# 2.net
KiCad netlist of a schematic drawn in Altium Designer
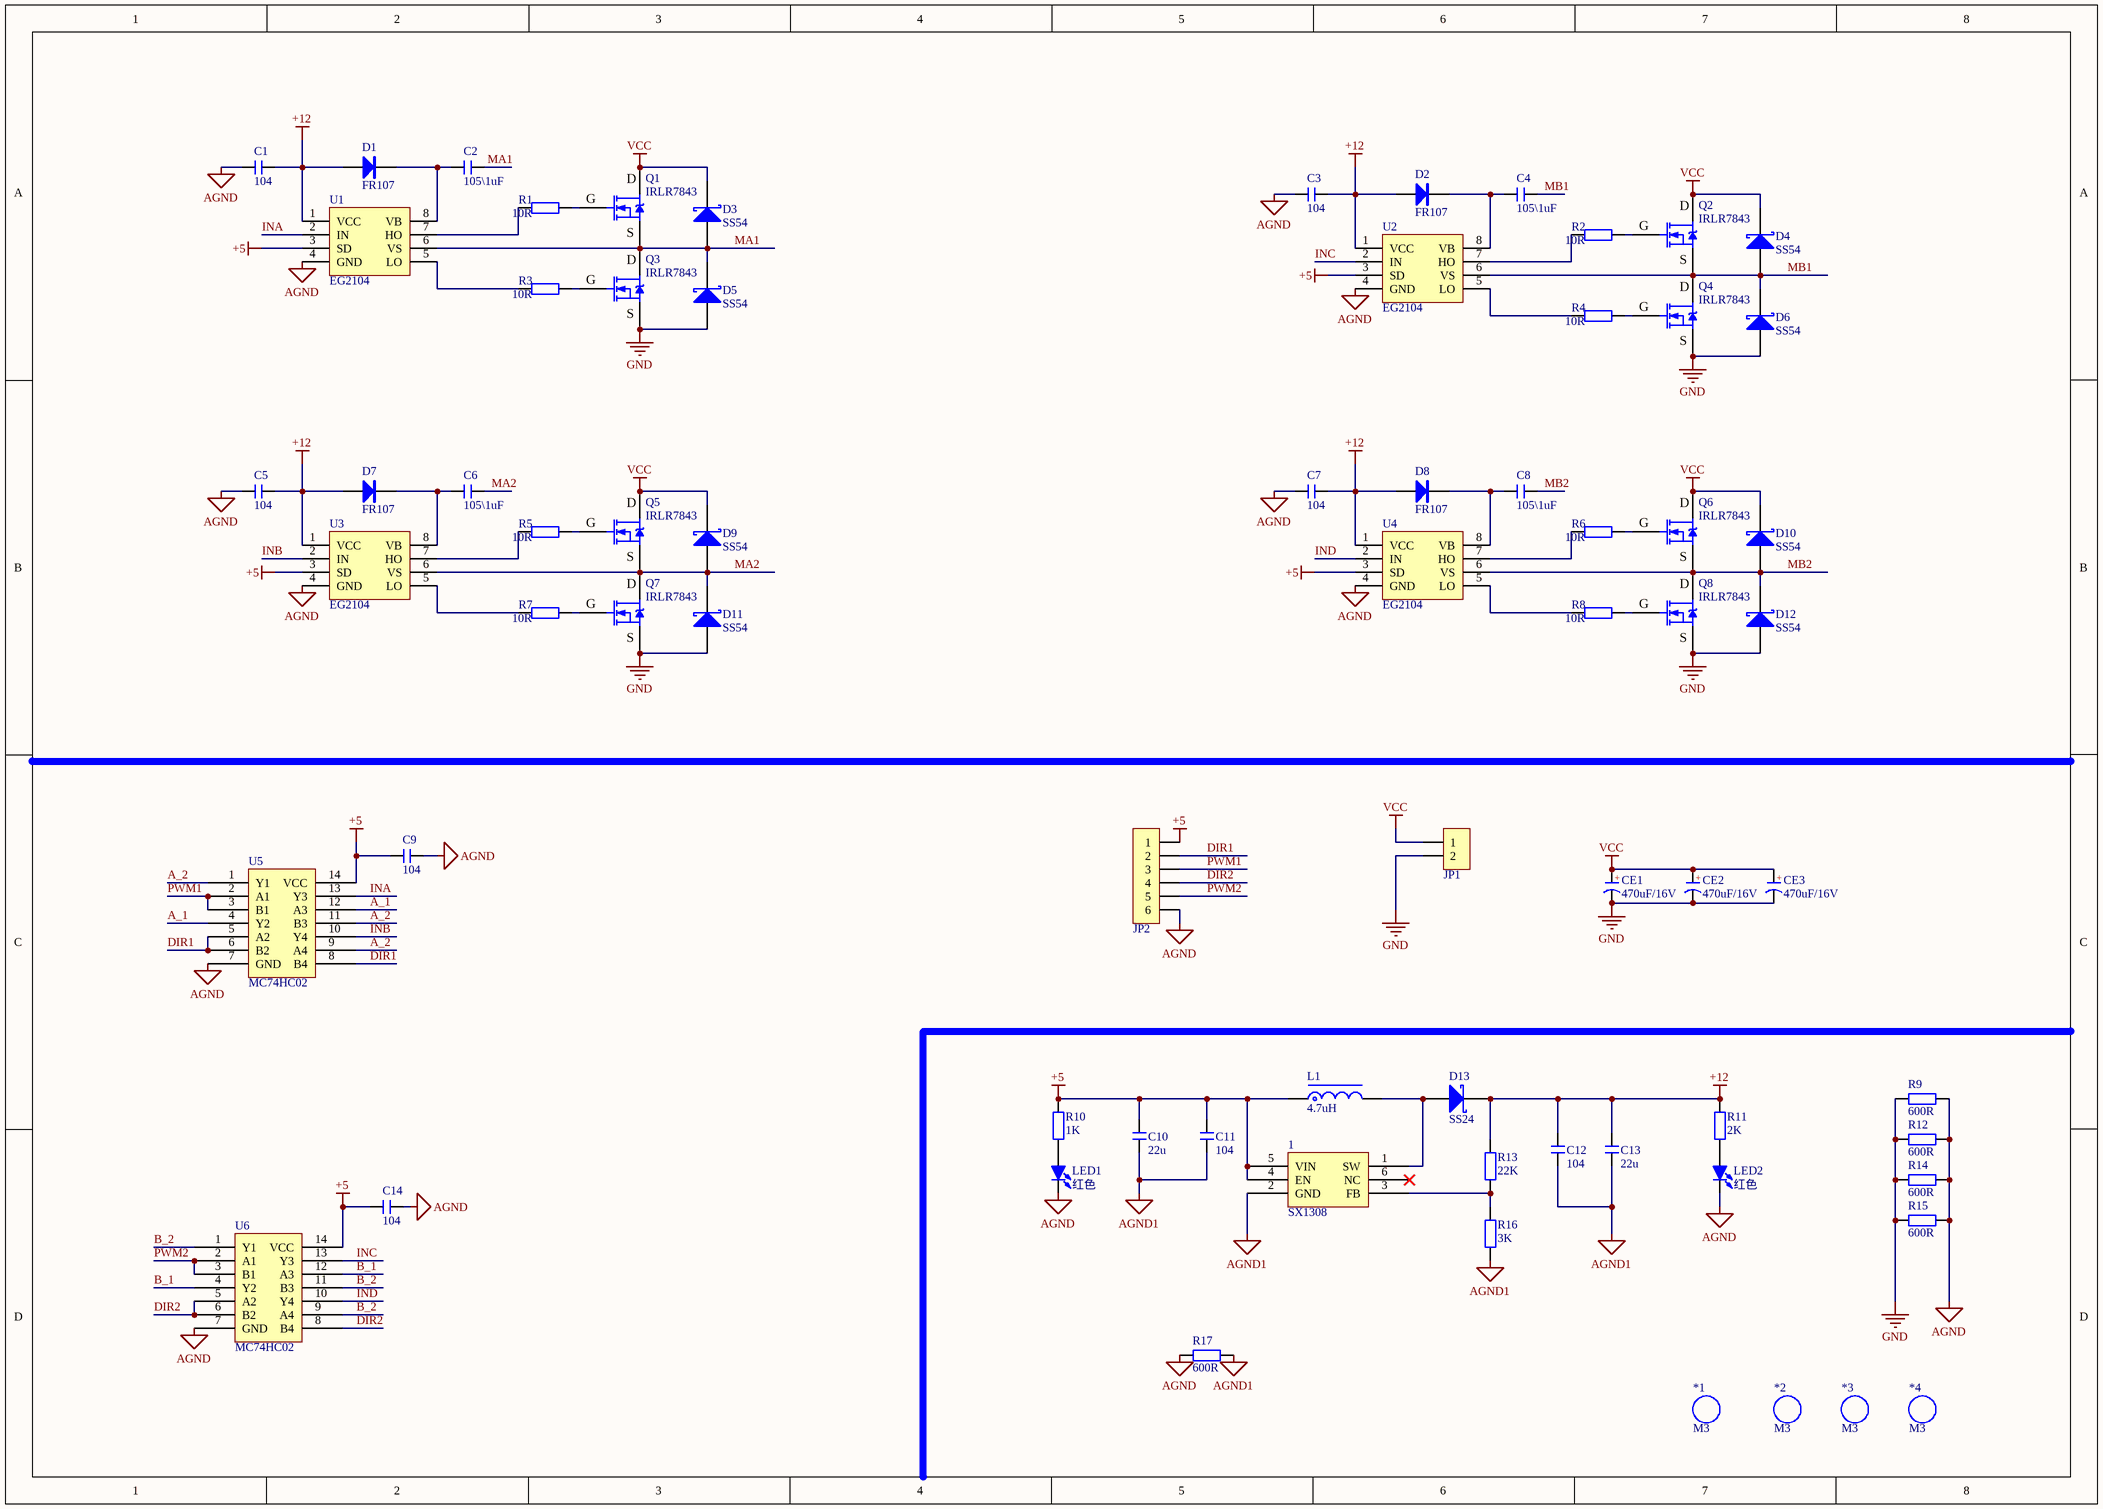
[diagram p0: 双电机驱动版本2.SchDoc]

(export (version "E")
  (design (tool "Eeschema 10.0.6"))
  (components
    (comp (ref "*1")
      (value "M3")
      (footprint "M3 125X200")
      (description "铜柱孔")
      (fields (field (name "版权归属") "封装库来自淘宝 ID：黄晶宝石"))
      (libsource (lib "4.1 - 未分类器件") (part "M3"))
    )
    (comp (ref "*2")
      (value "M3")
      (footprint "M3 125X200")
      (description "铜柱孔")
      (fields (field (name "版权归属") "封装库来自淘宝 ID：黄晶宝石"))
      (libsource (lib "4.1 - 未分类器件") (part "M3"))
    )
    (comp (ref "*3")
      (value "M3")
      (footprint "M3 125X200")
      (description "铜柱孔")
      (fields (field (name "版权归属") "封装库来自淘宝 ID：黄晶宝石"))
      (libsource (lib "4.1 - 未分类器件") (part "M3"))
    )
    (comp (ref "*4")
      (value "M3")
      (footprint "M3 125X200")
      (description "铜柱孔")
      (fields (field (name "版权归属") "封装库来自淘宝 ID：黄晶宝石"))
      (libsource (lib "4.1 - 未分类器件") (part "M3"))
    )
    (comp (ref "1") (value "SX1308") (footprint "SOT23-6L") (libsource (lib "boost电源5V") (part "SX1308")))
    (comp (ref "C1")
      (value "104")
      (footprint "C 0805_L")
      (description "贴片电容")
      (libsource (lib "0.1 - 电阻-电容-电感") (part "C"))
    )
    (comp (ref "C2")
      (value "10~{5}1uF")
      (footprint "C 0805_L")
      (description "贴片电容")
      (libsource (lib "0.1 - 电阻-电容-电感") (part "C"))
    )
    (comp (ref "C3")
      (value "104")
      (footprint "C 0805_L")
      (description "贴片电容")
      (libsource (lib "0.1 - 电阻-电容-电感") (part "C"))
    )
    (comp (ref "C4")
      (value "10~{5}1uF")
      (footprint "C 0805_L")
      (description "贴片电容")
      (libsource (lib "0.1 - 电阻-电容-电感") (part "C"))
    )
    (comp (ref "C5")
      (value "104")
      (footprint "C 0805_L")
      (description "贴片电容")
      (libsource (lib "0.1 - 电阻-电容-电感") (part "C"))
    )
    (comp (ref "C6")
      (value "10~{5}1uF")
      (footprint "C 0805_L")
      (description "贴片电容")
      (libsource (lib "0.1 - 电阻-电容-电感") (part "C"))
    )
    (comp (ref "C7")
      (value "104")
      (footprint "C 0805_L")
      (description "贴片电容")
      (libsource (lib "0.1 - 电阻-电容-电感") (part "C"))
    )
    (comp (ref "C8")
      (value "10~{5}1uF")
      (footprint "C 0805_L")
      (description "贴片电容")
      (libsource (lib "0.1 - 电阻-电容-电感") (part "C"))
    )
    (comp (ref "C9")
      (value "104")
      (footprint "C 0603_L")
      (description "贴片电容")
      (libsource (lib "0.1 - 电阻-电容-电感") (part "C"))
    )
    (comp (ref "C10")
      (value "22u")
      (footprint "C 0805_L")
      (description "贴片电容")
      (libsource (lib "0.1 - 电阻-电容-电感") (part "C"))
    )
    (comp (ref "C11")
      (value "104")
      (footprint "C 0603_L")
      (description "贴片电容")
      (libsource (lib "0.1 - 电阻-电容-电感") (part "C"))
    )
    (comp (ref "C12")
      (value "104")
      (footprint "C 0603_L")
      (description "贴片电容")
      (libsource (lib "0.1 - 电阻-电容-电感") (part "C"))
    )
    (comp (ref "C13")
      (value "22u")
      (footprint "C 0805_L")
      (description "贴片电容")
      (libsource (lib "0.1 - 电阻-电容-电感") (part "C"))
    )
    (comp (ref "C14")
      (value "104")
      (footprint "C 0603_L")
      (description "贴片电容")
      (libsource (lib "0.1 - 电阻-电容-电感") (part "C"))
    )
    (comp (ref "CE1")
      (value "470uF/16V")
      (footprint "CAP 3*8*12")
      (description "直插电解电容")
      (libsource (lib "0.1 - 电阻-电容-电感") (part "CE"))
    )
    (comp (ref "CE2")
      (value "470uF/16V")
      (footprint "CAP 3*8*12")
      (description "直插电解电容")
      (libsource (lib "0.1 - 电阻-电容-电感") (part "CE"))
    )
    (comp (ref "CE3")
      (value "470uF/16V")
      (footprint "CAP 3*8*12")
      (description "直插电解电容")
      (libsource (lib "0.1 - 电阻-电容-电感") (part "CE"))
    )
    (comp (ref "D1")
      (value "FR107")
      (footprint "SOD-123")
      (description "快恢复整流二极管")
      (fields (field (name "版权归属") "封装库来自淘宝 ID：黄晶宝石"))
      (libsource (lib "0.2 - 二极管-整流桥") (part "FR107"))
    )
    (comp (ref "D2")
      (value "FR107")
      (footprint "SOD-123")
      (description "快恢复整流二极管")
      (fields (field (name "版权归属") "封装库来自淘宝 ID：黄晶宝石"))
      (libsource (lib "0.2 - 二极管-整流桥") (part "FR107"))
    )
    (comp (ref "D3")
      (value "SS54")
      (footprint "SMA")
      (description "肖特基二极管")
      (libsource (lib "0.2 - 二极管-整流桥") (part "SS34"))
    )
    (comp (ref "D4")
      (value "SS54")
      (footprint "SMA")
      (description "肖特基二极管")
      (libsource (lib "0.2 - 二极管-整流桥") (part "SS34"))
    )
    (comp (ref "D5")
      (value "SS54")
      (footprint "SMA")
      (description "肖特基二极管")
      (libsource (lib "0.2 - 二极管-整流桥") (part "SS34"))
    )
    (comp (ref "D6")
      (value "SS54")
      (footprint "SMA")
      (description "肖特基二极管")
      (libsource (lib "0.2 - 二极管-整流桥") (part "SS34"))
    )
    (comp (ref "D7")
      (value "FR107")
      (footprint "SOD-123")
      (description "快恢复整流二极管")
      (fields (field (name "版权归属") "封装库来自淘宝 ID：黄晶宝石"))
      (libsource (lib "0.2 - 二极管-整流桥") (part "FR107"))
    )
    (comp (ref "D8")
      (value "FR107")
      (footprint "SOD-123")
      (description "快恢复整流二极管")
      (fields (field (name "版权归属") "封装库来自淘宝 ID：黄晶宝石"))
      (libsource (lib "0.2 - 二极管-整流桥") (part "FR107"))
    )
    (comp (ref "D9")
      (value "SS54")
      (footprint "SMA")
      (description "肖特基二极管")
      (libsource (lib "0.2 - 二极管-整流桥") (part "SS34"))
    )
    (comp (ref "D10")
      (value "SS54")
      (footprint "SMA")
      (description "肖特基二极管")
      (libsource (lib "0.2 - 二极管-整流桥") (part "SS34"))
    )
    (comp (ref "D11")
      (value "SS54")
      (footprint "SMA")
      (description "肖特基二极管")
      (libsource (lib "0.2 - 二极管-整流桥") (part "SS34"))
    )
    (comp (ref "D12")
      (value "SS54")
      (footprint "SMA")
      (description "肖特基二极管")
      (libsource (lib "0.2 - 二极管-整流桥") (part "SS34"))
    )
    (comp (ref "D13")
      (value "SS24")
      (footprint "SMA")
      (description "肖特基二极管")
      (libsource (lib "0.2 - 二极管-整流桥") (part "SS14"))
    )
    (comp (ref "JP1")
      (value "HDR-1X2")
      (footprint "XT30-M")
      (description "2P接插件")
      (fields (field (name "版权归属") "封装库来自淘宝卖家 ID：黄晶宝石"))
      (libsource (lib "6.1 - 接插件-脚距5.08 (200mil) ") (part "Header 2"))
    )
    (comp (ref "JP2")
      (value "HDR-1X6")
      (footprint "XH2.54-WI-6P")
      (description "6P接插件")
      (fields (field (name "版权归属") "封装库来自淘宝 ID：黄晶宝石"))
      (libsource (lib "5.4 - 接插件-脚距2.54 (100mil) ") (part "Header 6"))
    )
    (comp (ref "L1")
      (value "4.7uH")
      (footprint "CD43")
      (description "CD系列贴片线绕功率电感")
      (libsource (lib "0.1 - 电阻-电容-电感") (part "L-SMD"))
    )
    (comp (ref "LED1")
      (value "红色")
      (footprint "LED 0603G")
      (description "贴片LED")
      (fields (field (name "版权归属") "封装库来自淘宝 ID：黄晶宝石"))
      (libsource (lib "0.3 - LED发光二极管") (part "LED-SMD"))
    )
    (comp (ref "LED2")
      (value "红色")
      (footprint "LED 0603R")
      (description "贴片LED")
      (fields (field (name "版权归属") "封装库来自淘宝 ID：黄晶宝石"))
      (libsource (lib "0.3 - LED发光二极管") (part "LED-SMD"))
    )
    (comp (ref "Q1")
      (value "IRLR7843")
      (footprint "TO252")
      (description "N沟场效应管")
      (fields (field (name "版权归属") "封装库来自淘宝 ID：黄晶宝石"))
      (libsource (lib "0.5 - 场效应管-可控硅") (part "IRF3710"))
    )
    (comp (ref "Q2")
      (value "IRLR7843")
      (footprint "TO252")
      (description "N沟场效应管")
      (fields (field (name "版权归属") "封装库来自淘宝 ID：黄晶宝石"))
      (libsource (lib "0.5 - 场效应管-可控硅") (part "IRF3710"))
    )
    (comp (ref "Q3")
      (value "IRLR7843")
      (footprint "TO252")
      (description "N沟场效应管")
      (fields (field (name "版权归属") "封装库来自淘宝 ID：黄晶宝石"))
      (libsource (lib "0.5 - 场效应管-可控硅") (part "IRF3710"))
    )
    (comp (ref "Q4")
      (value "IRLR7843")
      (footprint "TO252")
      (description "N沟场效应管")
      (fields (field (name "版权归属") "封装库来自淘宝 ID：黄晶宝石"))
      (libsource (lib "0.5 - 场效应管-可控硅") (part "IRF3710"))
    )
    (comp (ref "Q5")
      (value "IRLR7843")
      (footprint "TO252")
      (description "N沟场效应管")
      (fields (field (name "版权归属") "封装库来自淘宝 ID：黄晶宝石"))
      (libsource (lib "0.5 - 场效应管-可控硅") (part "IRF3710"))
    )
    (comp (ref "Q6")
      (value "IRLR7843")
      (footprint "TO252")
      (description "N沟场效应管")
      (fields (field (name "版权归属") "封装库来自淘宝 ID：黄晶宝石"))
      (libsource (lib "0.5 - 场效应管-可控硅") (part "IRF3710"))
    )
    (comp (ref "Q7")
      (value "IRLR7843")
      (footprint "TO252")
      (description "N沟场效应管")
      (fields (field (name "版权归属") "封装库来自淘宝 ID：黄晶宝石"))
      (libsource (lib "0.5 - 场效应管-可控硅") (part "IRF3710"))
    )
    (comp (ref "Q8")
      (value "IRLR7843")
      (footprint "TO252")
      (description "N沟场效应管")
      (fields (field (name "版权归属") "封装库来自淘宝 ID：黄晶宝石"))
      (libsource (lib "0.5 - 场效应管-可控硅") (part "IRF3710"))
    )
    (comp (ref "R1")
      (value "10R")
      (footprint "R 0603_L")
      (description "贴片电阻")
      (fields (field (name "版权归属") "来自淘宝 ID：黄晶宝石"))
      (libsource (lib "0.1 - 电阻-电容-电感") (part "R"))
    )
    (comp (ref "R2")
      (value "10R")
      (footprint "R 0603_L")
      (description "贴片电阻")
      (fields (field (name "版权归属") "来自淘宝 ID：黄晶宝石"))
      (libsource (lib "0.1 - 电阻-电容-电感") (part "R"))
    )
    (comp (ref "R3")
      (value "10R")
      (footprint "R 0603_L")
      (description "贴片电阻")
      (fields (field (name "版权归属") "来自淘宝 ID：黄晶宝石"))
      (libsource (lib "0.1 - 电阻-电容-电感") (part "R"))
    )
    (comp (ref "R4")
      (value "10R")
      (footprint "R 0603_L")
      (description "贴片电阻")
      (fields (field (name "版权归属") "来自淘宝 ID：黄晶宝石"))
      (libsource (lib "0.1 - 电阻-电容-电感") (part "R"))
    )
    (comp (ref "R5")
      (value "10R")
      (footprint "R 0603_L")
      (description "贴片电阻")
      (fields (field (name "版权归属") "来自淘宝 ID：黄晶宝石"))
      (libsource (lib "0.1 - 电阻-电容-电感") (part "R"))
    )
    (comp (ref "R6")
      (value "10R")
      (footprint "R 0603_L")
      (description "贴片电阻")
      (fields (field (name "版权归属") "来自淘宝 ID：黄晶宝石"))
      (libsource (lib "0.1 - 电阻-电容-电感") (part "R"))
    )
    (comp (ref "R7")
      (value "10R")
      (footprint "R 0603_L")
      (description "贴片电阻")
      (fields (field (name "版权归属") "来自淘宝 ID：黄晶宝石"))
      (libsource (lib "0.1 - 电阻-电容-电感") (part "R"))
    )
    (comp (ref "R8")
      (value "10R")
      (footprint "R 0603_L")
      (description "贴片电阻")
      (fields (field (name "版权归属") "来自淘宝 ID：黄晶宝石"))
      (libsource (lib "0.1 - 电阻-电容-电感") (part "R"))
    )
    (comp (ref "R9")
      (value "600R")
      (footprint "R 0603_L")
      (description "磁珠")
      (fields (field (name "版权归属") "来自淘宝 ID：黄晶宝石"))
      (libsource (lib "0.1 - 电阻-电容-电感") (part "R"))
    )
    (comp (ref "R10")
      (value "1K")
      (footprint "R 0603_L")
      (description "贴片电阻")
      (fields (field (name "版权归属") "来自淘宝 ID：黄晶宝石"))
      (libsource (lib "0.1 - 电阻-电容-电感") (part "R"))
    )
    (comp (ref "R11")
      (value "2K")
      (footprint "R 0603_L")
      (description "贴片电阻")
      (fields (field (name "版权归属") "来自淘宝 ID：黄晶宝石"))
      (libsource (lib "0.1 - 电阻-电容-电感") (part "R"))
    )
    (comp (ref "R12")
      (value "600R")
      (footprint "R 0603_L")
      (description "磁珠")
      (fields (field (name "版权归属") "来自淘宝 ID：黄晶宝石"))
      (libsource (lib "0.1 - 电阻-电容-电感") (part "R"))
    )
    (comp (ref "R13")
      (value "22K")
      (footprint "R 0603_L")
      (description "贴片电阻")
      (fields (field (name "版权归属") "来自淘宝 ID：黄晶宝石"))
      (libsource (lib "0.1 - 电阻-电容-电感") (part "R"))
    )
    (comp (ref "R14")
      (value "600R")
      (footprint "R 0603_L")
      (description "磁珠")
      (fields (field (name "版权归属") "来自淘宝 ID：黄晶宝石"))
      (libsource (lib "0.1 - 电阻-电容-电感") (part "R"))
    )
    (comp (ref "R15")
      (value "600R")
      (footprint "R 0603_L")
      (description "磁珠")
      (fields (field (name "版权归属") "来自淘宝 ID：黄晶宝石"))
      (libsource (lib "0.1 - 电阻-电容-电感") (part "R"))
    )
    (comp (ref "R16")
      (value "3K")
      (footprint "R 0603_L")
      (description "贴片电阻")
      (fields (field (name "版权归属") "来自淘宝 ID：黄晶宝石"))
      (libsource (lib "0.1 - 电阻-电容-电感") (part "R"))
    )
    (comp (ref "R17")
      (value "600R")
      (footprint "R 0603_L")
      (description "磁珠")
      (fields (field (name "版权归属") "来自淘宝 ID：黄晶宝石"))
      (libsource (lib "0.1 - 电阻-电容-电感") (part "R"))
    )
    (comp (ref "U1")
      (value "EG2104")
      (footprint "SOP8")
      (description "半桥驱动芯片")
      (libsource (lib "1.1 - 电源类芯片") (part "EG2104"))
    )
    (comp (ref "U2")
      (value "EG2104")
      (footprint "SOP8")
      (description "半桥驱动芯片")
      (libsource (lib "1.1 - 电源类芯片") (part "EG2104"))
    )
    (comp (ref "U3")
      (value "EG2104")
      (footprint "SOP8")
      (description "半桥驱动芯片")
      (libsource (lib "1.1 - 电源类芯片") (part "EG2104"))
    )
    (comp (ref "U4")
      (value "EG2104")
      (footprint "SOP8")
      (description "半桥驱动芯片")
      (libsource (lib "1.1 - 电源类芯片") (part "EG2104"))
    )
    (comp (ref "U5")
      (value "MC74HC02")
      (footprint "SOP14_N")
      (description "或非门")
      (libsource (lib "智能车驱动-双电机-版本1") (part "MC74HC02"))
    )
    (comp (ref "U6")
      (value "MC74HC02")
      (footprint "SOP14_N")
      (description "或非门")
      (libsource (lib "智能车驱动-双电机-版本1") (part "MC74HC02"))
    )
  )
  (nets
    (net (code "1") (name "+5") (class "Default")
      (node (ref "1") (pin "4") (pinfunction "EN_4") (pintype "passive"))
      (node (ref "1") (pin "5") (pinfunction "VIN_5") (pintype "passive"))
      (node (ref "C10") (pin "2") (pinfunction "2_2") (pintype "passive"))
      (node (ref "C11") (pin "2") (pinfunction "2_2") (pintype "passive"))
      (node (ref "C14") (pin "1") (pinfunction "1_1") (pintype "passive"))
      (node (ref "C9") (pin "1") (pinfunction "1_1") (pintype "passive"))
      (node (ref "JP2") (pin "1") (pinfunction "1_1") (pintype "passive"))
      (node (ref "L1") (pin "1") (pinfunction "1_1") (pintype "passive"))
      (node (ref "R10") (pin "2") (pinfunction "2_2") (pintype "passive"))
      (node (ref "U1") (pin "3") (pinfunction "SD_3") (pintype "passive"))
      (node (ref "U2") (pin "3") (pinfunction "SD_3") (pintype "passive"))
      (node (ref "U3") (pin "3") (pinfunction "SD_3") (pintype "passive"))
      (node (ref "U4") (pin "3") (pinfunction "SD_3") (pintype "passive"))
      (node (ref "U5") (pin "14") (pinfunction "VCC_14") (pintype "passive"))
      (node (ref "U6") (pin "14") (pinfunction "VCC_14") (pintype "passive"))
    )
    (net (code "2") (name "+12") (class "Default")
      (node (ref "C1") (pin "2") (pinfunction "2_2") (pintype "passive"))
      (node (ref "C12") (pin "2") (pinfunction "2_2") (pintype "passive"))
      (node (ref "C13") (pin "2") (pinfunction "2_2") (pintype "passive"))
      (node (ref "C3") (pin "2") (pinfunction "2_2") (pintype "passive"))
      (node (ref "C5") (pin "2") (pinfunction "2_2") (pintype "passive"))
      (node (ref "C7") (pin "2") (pinfunction "2_2") (pintype "passive"))
      (node (ref "D1") (pin "1") (pinfunction "A_1") (pintype "passive"))
      (node (ref "D13") (pin "2") (pinfunction "K_2") (pintype "passive"))
      (node (ref "D2") (pin "1") (pinfunction "A_1") (pintype "passive"))
      (node (ref "D7") (pin "1") (pinfunction "A_1") (pintype "passive"))
      (node (ref "D8") (pin "1") (pinfunction "A_1") (pintype "passive"))
      (node (ref "R11") (pin "2") (pinfunction "2_2") (pintype "passive"))
      (node (ref "R13") (pin "2") (pinfunction "2_2") (pintype "passive"))
      (node (ref "U1") (pin "1") (pinfunction "VCC_1") (pintype "passive"))
      (node (ref "U2") (pin "1") (pinfunction "VCC_1") (pintype "passive"))
      (node (ref "U3") (pin "1") (pinfunction "VCC_1") (pintype "passive"))
      (node (ref "U4") (pin "1") (pinfunction "VCC_1") (pintype "passive"))
    )
    (net (code "3") (name "/A_1") (class "Default")
      (node (ref "U5") (pin "12") (pinfunction "A3_12") (pintype "passive"))
      (node (ref "U5") (pin "4") (pinfunction "Y2_4") (pintype "passive"))
    )
    (net (code "4") (name "/A_2") (class "Default")
      (node (ref "U5") (pin "1") (pinfunction "Y1_1") (pintype "passive"))
      (node (ref "U5") (pin "11") (pinfunction "B3_11") (pintype "passive"))
      (node (ref "U5") (pin "9") (pinfunction "A4_9") (pintype "passive"))
    )
    (net (code "5") (name "/B_1") (class "Default")
      (node (ref "U6") (pin "12") (pinfunction "A3_12") (pintype "passive"))
      (node (ref "U6") (pin "4") (pinfunction "Y2_4") (pintype "passive"))
    )
    (net (code "6") (name "/B_2") (class "Default")
      (node (ref "U6") (pin "1") (pinfunction "Y1_1") (pintype "passive"))
      (node (ref "U6") (pin "11") (pinfunction "B3_11") (pintype "passive"))
      (node (ref "U6") (pin "9") (pinfunction "A4_9") (pintype "passive"))
    )
    (net (code "7") (name "/DIR1") (class "Default")
      (node (ref "JP2") (pin "2") (pinfunction "2_2") (pintype "passive"))
      (node (ref "U5") (pin "5") (pinfunction "A2_5") (pintype "passive"))
      (node (ref "U5") (pin "6") (pinfunction "B2_6") (pintype "passive"))
      (node (ref "U5") (pin "8") (pinfunction "B4_8") (pintype "passive"))
    )
    (net (code "8") (name "/DIR2") (class "Default")
      (node (ref "JP2") (pin "4") (pinfunction "4_4") (pintype "passive"))
      (node (ref "U6") (pin "5") (pinfunction "A2_5") (pintype "passive"))
      (node (ref "U6") (pin "6") (pinfunction "B2_6") (pintype "passive"))
      (node (ref "U6") (pin "8") (pinfunction "B4_8") (pintype "passive"))
    )
    (net (code "9") (name "/INA") (class "Default")
      (node (ref "U1") (pin "2") (pinfunction "IN_2") (pintype "passive"))
      (node (ref "U5") (pin "13") (pinfunction "Y3_13") (pintype "passive"))
    )
    (net (code "10") (name "/INB") (class "Default")
      (node (ref "U3") (pin "2") (pinfunction "IN_2") (pintype "passive"))
      (node (ref "U5") (pin "10") (pinfunction "Y4_10") (pintype "passive"))
    )
    (net (code "11") (name "/INC") (class "Default")
      (node (ref "U2") (pin "2") (pinfunction "IN_2") (pintype "passive"))
      (node (ref "U6") (pin "13") (pinfunction "Y3_13") (pintype "passive"))
    )
    (net (code "12") (name "/IND") (class "Default")
      (node (ref "U4") (pin "2") (pinfunction "IN_2") (pintype "passive"))
      (node (ref "U6") (pin "10") (pinfunction "Y4_10") (pintype "passive"))
    )
    (net (code "13") (name "/MA1") (class "Default")
      (node (ref "C2") (pin "1") (pinfunction "1_1") (pintype "passive"))
      (node (ref "D3") (pin "1") (pinfunction "A_1") (pintype "passive"))
      (node (ref "D5") (pin "2") (pinfunction "K_2") (pintype "passive"))
      (node (ref "Q1") (pin "3") (pinfunction "S_3") (pintype "passive"))
      (node (ref "Q3") (pin "2") (pinfunction "D_2") (pintype "passive"))
      (node (ref "U1") (pin "6") (pinfunction "VS_6") (pintype "passive"))
    )
    (net (code "14") (name "/MA2") (class "Default")
      (node (ref "C6") (pin "1") (pinfunction "1_1") (pintype "passive"))
      (node (ref "D11") (pin "2") (pinfunction "K_2") (pintype "passive"))
      (node (ref "D9") (pin "1") (pinfunction "A_1") (pintype "passive"))
      (node (ref "Q5") (pin "3") (pinfunction "S_3") (pintype "passive"))
      (node (ref "Q7") (pin "2") (pinfunction "D_2") (pintype "passive"))
      (node (ref "U3") (pin "6") (pinfunction "VS_6") (pintype "passive"))
    )
    (net (code "15") (name "/MB1") (class "Default")
      (node (ref "C4") (pin "1") (pinfunction "1_1") (pintype "passive"))
      (node (ref "D4") (pin "1") (pinfunction "A_1") (pintype "passive"))
      (node (ref "D6") (pin "2") (pinfunction "K_2") (pintype "passive"))
      (node (ref "Q2") (pin "3") (pinfunction "S_3") (pintype "passive"))
      (node (ref "Q4") (pin "2") (pinfunction "D_2") (pintype "passive"))
      (node (ref "U2") (pin "6") (pinfunction "VS_6") (pintype "passive"))
    )
    (net (code "16") (name "/MB2") (class "Default")
      (node (ref "C8") (pin "1") (pinfunction "1_1") (pintype "passive"))
      (node (ref "D10") (pin "1") (pinfunction "A_1") (pintype "passive"))
      (node (ref "D12") (pin "2") (pinfunction "K_2") (pintype "passive"))
      (node (ref "Q6") (pin "3") (pinfunction "S_3") (pintype "passive"))
      (node (ref "Q8") (pin "2") (pinfunction "D_2") (pintype "passive"))
      (node (ref "U4") (pin "6") (pinfunction "VS_6") (pintype "passive"))
    )
    (net (code "17") (name "/PWM1") (class "Default")
      (node (ref "JP2") (pin "3") (pinfunction "3_3") (pintype "passive"))
      (node (ref "U5") (pin "2") (pinfunction "A1_2") (pintype "passive"))
      (node (ref "U5") (pin "3") (pinfunction "B1_3") (pintype "passive"))
    )
    (net (code "18") (name "/PWM2") (class "Default")
      (node (ref "JP2") (pin "5") (pinfunction "5_5") (pintype "passive"))
      (node (ref "U6") (pin "2") (pinfunction "A1_2") (pintype "passive"))
      (node (ref "U6") (pin "3") (pinfunction "B1_3") (pintype "passive"))
    )
    (net (code "19") (name "AGND") (class "Default")
      (node (ref "C1") (pin "1") (pinfunction "1_1") (pintype "passive"))
      (node (ref "C14") (pin "2") (pinfunction "2_2") (pintype "passive"))
      (node (ref "C3") (pin "1") (pinfunction "1_1") (pintype "passive"))
      (node (ref "C5") (pin "1") (pinfunction "1_1") (pintype "passive"))
      (node (ref "C7") (pin "1") (pinfunction "1_1") (pintype "passive"))
      (node (ref "C9") (pin "2") (pinfunction "2_2") (pintype "passive"))
      (node (ref "JP2") (pin "6") (pinfunction "6_6") (pintype "passive"))
      (node (ref "LED1") (pin "2") (pinfunction "K_2") (pintype "passive"))
      (node (ref "LED2") (pin "2") (pinfunction "K_2") (pintype "passive"))
      (node (ref "R12") (pin "2") (pinfunction "2_2") (pintype "passive"))
      (node (ref "R14") (pin "2") (pinfunction "2_2") (pintype "passive"))
      (node (ref "R15") (pin "2") (pinfunction "2_2") (pintype "passive"))
      (node (ref "R17") (pin "1") (pinfunction "1_1") (pintype "passive"))
      (node (ref "R9") (pin "2") (pinfunction "2_2") (pintype "passive"))
      (node (ref "U1") (pin "4") (pinfunction "GND_4") (pintype "passive"))
      (node (ref "U2") (pin "4") (pinfunction "GND_4") (pintype "passive"))
      (node (ref "U3") (pin "4") (pinfunction "GND_4") (pintype "passive"))
      (node (ref "U4") (pin "4") (pinfunction "GND_4") (pintype "passive"))
      (node (ref "U5") (pin "7") (pinfunction "GND_7") (pintype "passive"))
      (node (ref "U6") (pin "7") (pinfunction "GND_7") (pintype "passive"))
    )
    (net (code "20") (name "AGND1") (class "Default")
      (node (ref "1") (pin "2") (pinfunction "GND_2") (pintype "passive"))
      (node (ref "C10") (pin "1") (pinfunction "1_1") (pintype "passive"))
      (node (ref "C11") (pin "1") (pinfunction "1_1") (pintype "passive"))
      (node (ref "C12") (pin "1") (pinfunction "1_1") (pintype "passive"))
      (node (ref "C13") (pin "1") (pinfunction "1_1") (pintype "passive"))
      (node (ref "R16") (pin "1") (pinfunction "1_1") (pintype "passive"))
      (node (ref "R17") (pin "2") (pinfunction "2_2") (pintype "passive"))
    )
    (net (code "21") (name "GND") (class "Default")
      (node (ref "CE1") (pin "2") (pinfunction "K_2") (pintype "passive"))
      (node (ref "CE2") (pin "2") (pinfunction "K_2") (pintype "passive"))
      (node (ref "CE3") (pin "2") (pinfunction "K_2") (pintype "passive"))
      (node (ref "D11") (pin "1") (pinfunction "A_1") (pintype "passive"))
      (node (ref "D12") (pin "1") (pinfunction "A_1") (pintype "passive"))
      (node (ref "D5") (pin "1") (pinfunction "A_1") (pintype "passive"))
      (node (ref "D6") (pin "1") (pinfunction "A_1") (pintype "passive"))
      (node (ref "JP1") (pin "2") (pinfunction "2_2") (pintype "passive"))
      (node (ref "Q3") (pin "3") (pinfunction "S_3") (pintype "passive"))
      (node (ref "Q4") (pin "3") (pinfunction "S_3") (pintype "passive"))
      (node (ref "Q7") (pin "3") (pinfunction "S_3") (pintype "passive"))
      (node (ref "Q8") (pin "3") (pinfunction "S_3") (pintype "passive"))
      (node (ref "R12") (pin "1") (pinfunction "1_1") (pintype "passive"))
      (node (ref "R14") (pin "1") (pinfunction "1_1") (pintype "passive"))
      (node (ref "R15") (pin "1") (pinfunction "1_1") (pintype "passive"))
      (node (ref "R9") (pin "1") (pinfunction "1_1") (pintype "passive"))
    )
    (net (code "22") (name "Net-(1-FB)") (class "Default")
      (node (ref "1") (pin "3") (pinfunction "FB_3") (pintype "passive"))
      (node (ref "R13") (pin "1") (pinfunction "1_1") (pintype "passive"))
      (node (ref "R16") (pin "2") (pinfunction "2_2") (pintype "passive"))
    )
    (net (code "23") (name "Net-(1-SW)") (class "Default")
      (node (ref "1") (pin "1") (pinfunction "SW_1") (pintype "passive"))
      (node (ref "D13") (pin "1") (pinfunction "A_1") (pintype "passive"))
      (node (ref "L1") (pin "2") (pinfunction "2_2") (pintype "passive"))
    )
    (net (code "24") (name "Net-(D1-K)") (class "Default")
      (node (ref "C2") (pin "2") (pinfunction "2_2") (pintype "passive"))
      (node (ref "D1") (pin "2") (pinfunction "K_2") (pintype "passive"))
      (node (ref "U1") (pin "8") (pinfunction "VB_8") (pintype "passive"))
    )
    (net (code "25") (name "Net-(D2-K)") (class "Default")
      (node (ref "C4") (pin "2") (pinfunction "2_2") (pintype "passive"))
      (node (ref "D2") (pin "2") (pinfunction "K_2") (pintype "passive"))
      (node (ref "U2") (pin "8") (pinfunction "VB_8") (pintype "passive"))
    )
    (net (code "26") (name "Net-(D7-K)") (class "Default")
      (node (ref "C6") (pin "2") (pinfunction "2_2") (pintype "passive"))
      (node (ref "D7") (pin "2") (pinfunction "K_2") (pintype "passive"))
      (node (ref "U3") (pin "8") (pinfunction "VB_8") (pintype "passive"))
    )
    (net (code "27") (name "Net-(D8-K)") (class "Default")
      (node (ref "C8") (pin "2") (pinfunction "2_2") (pintype "passive"))
      (node (ref "D8") (pin "2") (pinfunction "K_2") (pintype "passive"))
      (node (ref "U4") (pin "8") (pinfunction "VB_8") (pintype "passive"))
    )
    (net (code "28") (name "Net-(LED1-A)") (class "Default")
      (node (ref "LED1") (pin "1") (pinfunction "A_1") (pintype "passive"))
      (node (ref "R10") (pin "1") (pinfunction "1_1") (pintype "passive"))
    )
    (net (code "29") (name "Net-(LED2-A)") (class "Default")
      (node (ref "LED2") (pin "1") (pinfunction "A_1") (pintype "passive"))
      (node (ref "R11") (pin "1") (pinfunction "1_1") (pintype "passive"))
    )
    (net (code "30") (name "Net-(Q1-G)") (class "Default")
      (node (ref "Q1") (pin "1") (pinfunction "G_1") (pintype "passive"))
      (node (ref "R1") (pin "1") (pinfunction "1_1") (pintype "passive"))
    )
    (net (code "31") (name "Net-(Q2-G)") (class "Default")
      (node (ref "Q2") (pin "1") (pinfunction "G_1") (pintype "passive"))
      (node (ref "R2") (pin "1") (pinfunction "1_1") (pintype "passive"))
    )
    (net (code "32") (name "Net-(Q3-G)") (class "Default")
      (node (ref "Q3") (pin "1") (pinfunction "G_1") (pintype "passive"))
      (node (ref "R3") (pin "1") (pinfunction "1_1") (pintype "passive"))
    )
    (net (code "33") (name "Net-(Q4-G)") (class "Default")
      (node (ref "Q4") (pin "1") (pinfunction "G_1") (pintype "passive"))
      (node (ref "R4") (pin "1") (pinfunction "1_1") (pintype "passive"))
    )
    (net (code "34") (name "Net-(Q5-G)") (class "Default")
      (node (ref "Q5") (pin "1") (pinfunction "G_1") (pintype "passive"))
      (node (ref "R5") (pin "1") (pinfunction "1_1") (pintype "passive"))
    )
    (net (code "35") (name "Net-(Q6-G)") (class "Default")
      (node (ref "Q6") (pin "1") (pinfunction "G_1") (pintype "passive"))
      (node (ref "R6") (pin "1") (pinfunction "1_1") (pintype "passive"))
    )
    (net (code "36") (name "Net-(Q7-G)") (class "Default")
      (node (ref "Q7") (pin "1") (pinfunction "G_1") (pintype "passive"))
      (node (ref "R7") (pin "1") (pinfunction "1_1") (pintype "passive"))
    )
    (net (code "37") (name "Net-(Q8-G)") (class "Default")
      (node (ref "Q8") (pin "1") (pinfunction "G_1") (pintype "passive"))
      (node (ref "R8") (pin "1") (pinfunction "1_1") (pintype "passive"))
    )
    (net (code "38") (name "Net-(U1-HO)") (class "Default")
      (node (ref "R1") (pin "2") (pinfunction "2_2") (pintype "passive"))
      (node (ref "U1") (pin "7") (pinfunction "HO_7") (pintype "passive"))
    )
    (net (code "39") (name "Net-(U1-LO)") (class "Default")
      (node (ref "R3") (pin "2") (pinfunction "2_2") (pintype "passive"))
      (node (ref "U1") (pin "5") (pinfunction "LO_5") (pintype "passive"))
    )
    (net (code "40") (name "Net-(U2-HO)") (class "Default")
      (node (ref "R2") (pin "2") (pinfunction "2_2") (pintype "passive"))
      (node (ref "U2") (pin "7") (pinfunction "HO_7") (pintype "passive"))
    )
    (net (code "41") (name "Net-(U2-LO)") (class "Default")
      (node (ref "R4") (pin "2") (pinfunction "2_2") (pintype "passive"))
      (node (ref "U2") (pin "5") (pinfunction "LO_5") (pintype "passive"))
    )
    (net (code "42") (name "Net-(U3-HO)") (class "Default")
      (node (ref "R5") (pin "2") (pinfunction "2_2") (pintype "passive"))
      (node (ref "U3") (pin "7") (pinfunction "HO_7") (pintype "passive"))
    )
    (net (code "43") (name "Net-(U3-LO)") (class "Default")
      (node (ref "R7") (pin "2") (pinfunction "2_2") (pintype "passive"))
      (node (ref "U3") (pin "5") (pinfunction "LO_5") (pintype "passive"))
    )
    (net (code "44") (name "Net-(U4-HO)") (class "Default")
      (node (ref "R6") (pin "2") (pinfunction "2_2") (pintype "passive"))
      (node (ref "U4") (pin "7") (pinfunction "HO_7") (pintype "passive"))
    )
    (net (code "45") (name "Net-(U4-LO)") (class "Default")
      (node (ref "R8") (pin "2") (pinfunction "2_2") (pintype "passive"))
      (node (ref "U4") (pin "5") (pinfunction "LO_5") (pintype "passive"))
    )
    (net (code "46") (name "VCC") (class "Default")
      (node (ref "CE1") (pin "1") (pinfunction "A_1") (pintype "passive"))
      (node (ref "CE2") (pin "1") (pinfunction "A_1") (pintype "passive"))
      (node (ref "CE3") (pin "1") (pinfunction "A_1") (pintype "passive"))
      (node (ref "D10") (pin "2") (pinfunction "K_2") (pintype "passive"))
      (node (ref "D3") (pin "2") (pinfunction "K_2") (pintype "passive"))
      (node (ref "D4") (pin "2") (pinfunction "K_2") (pintype "passive"))
      (node (ref "D9") (pin "2") (pinfunction "K_2") (pintype "passive"))
      (node (ref "JP1") (pin "1") (pinfunction "1_1") (pintype "passive"))
      (node (ref "Q1") (pin "2") (pinfunction "D_2") (pintype "passive"))
      (node (ref "Q2") (pin "2") (pinfunction "D_2") (pintype "passive"))
      (node (ref "Q5") (pin "2") (pinfunction "D_2") (pintype "passive"))
      (node (ref "Q6") (pin "2") (pinfunction "D_2") (pintype "passive"))
    )
    (net (code "47") (name "unconnected-(1-NC-Pad6)") (class "Default")
      (node (ref "1") (pin "6") (pinfunction "NC_6") (pintype "passive+no_connect"))
    )
  )
)
